# TSAL.net
KiCad netlist of a schematic drawn in Altium Designer
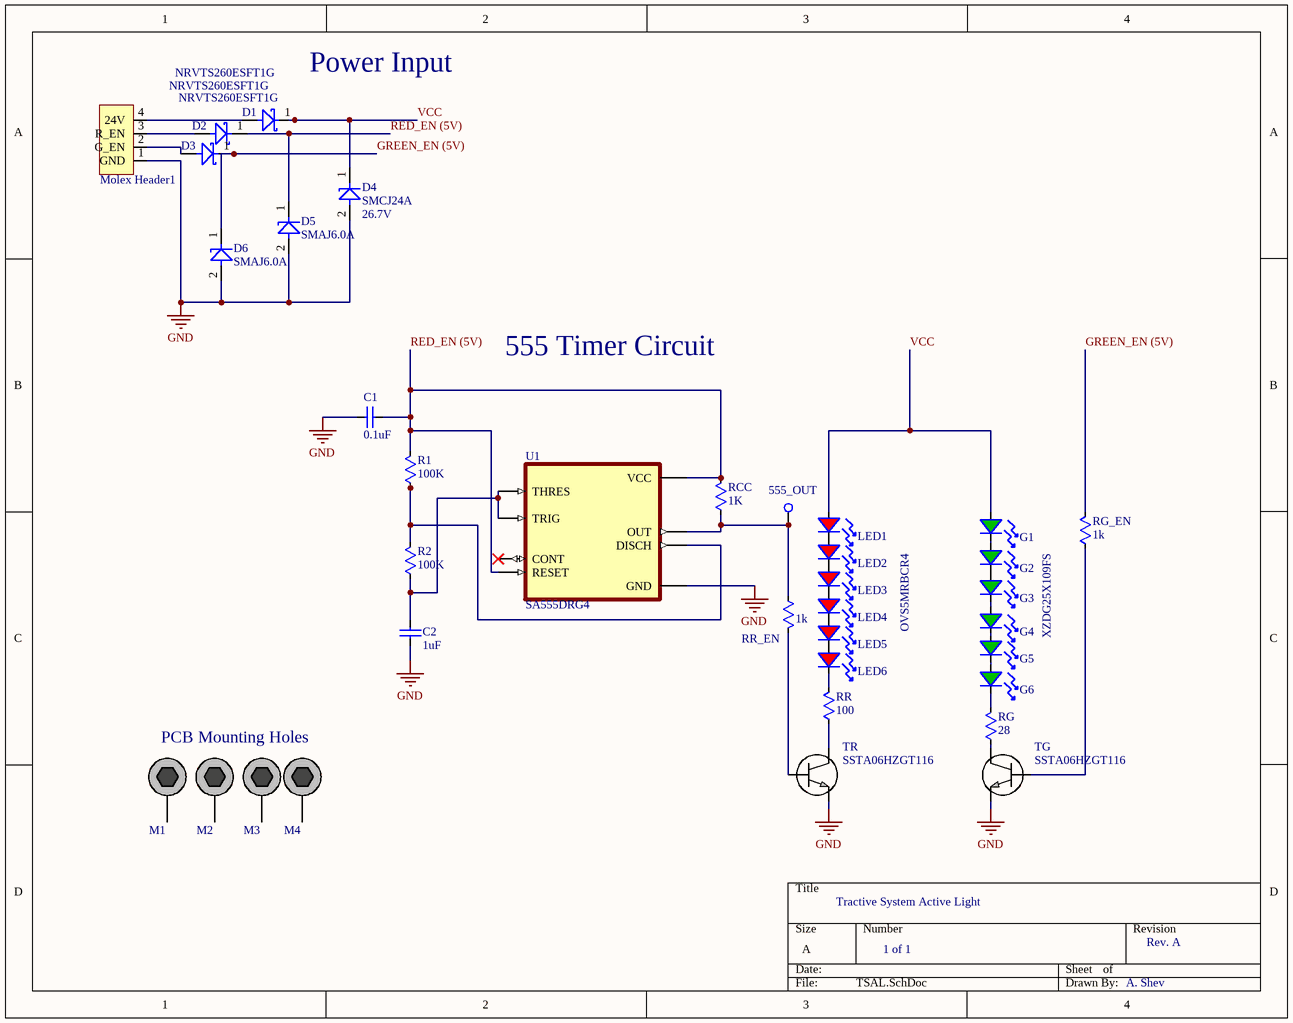
[diagram p0: TSAL.SchDoc]

(export (version "E")
  (design (tool "Eeschema 10.0.6"))
  (components
    (comp (ref "555_OUT")
      (value "Thru-Hole Test Point")
      (footprint "TESTPOINT (THROUGH-HOLE)")
      (libsource (lib "UBC Formula Electric") (part "Thru-Hole Test Point"))
    )
    (comp (ref "C1")
      (value "0.1uF")
      (footprint "0603 CAPACITOR (TDK C-SERIES)")
      (fields (field (name "Comment") "0603"))
      (libsource (lib "UBC Formula Electric") (part "0603 Ceramic Capacitor"))
    )
    (comp (ref "C2")
      (value "1uF")
      (footprint "0603 CAPACITOR (TDK C-SERIES)")
      (description "CAP CER 1UF 25V X5R 0603")
      (fields (field (name "Comment") "0603 CL10A105KA8NNNC"))
      (libsource (lib "UBC Formula Electric") (part "0603 Ceramic Capacitor"))
    )
    (comp (ref "D1")
      (value "NRVTS260ESFT1G")
      (footprint "ON NRVTS260ESFT1G")
      (description "Diode Schottky 60V 2A Surface Mount SOD-123FL")
      (libsource (lib "TSAL_2019_A") (part "ON NRVTS260ESFT1G"))
    )
    (comp (ref "D2")
      (value "NRVTS260ESFT1G")
      (footprint "ON NRVTS260ESFT1G")
      (description "Diode Schottky 60V 2A Surface Mount SOD-123FL")
      (libsource (lib "TSAL_2019_A") (part "ON NRVTS260ESFT1G"))
    )
    (comp (ref "D3")
      (value "NRVTS260ESFT1G")
      (footprint "ON NRVTS260ESFT1G")
      (description "Diode Schottky 60V 2A Surface Mount SOD-123FL")
      (libsource (lib "TSAL_2019_A") (part "ON NRVTS260ESFT1G"))
    )
    (comp (ref "D4")
      (value "SMCJ24A")
      (footprint "LITTELFUSE SMCJ24A")
      (description "38.9V Clamp 38.6A Ipp Tvs Diode Surface Mount DO-214AB (SMCJ)")
      (fields (field (name "ALTIUM_VALUE") "26.7V"))
      (libsource (lib "TSAL_2019_A") (part "Littelfuse SMCJ24A"))
    )
    (comp (ref "D5")
      (value "SMAJ6.0A")
      (footprint "LITTELFUSE SMAJ6.0A")
      (description "10.3V Clamp 38.8A Ipp Tvs Diode Surface Mount DO-214AC (SMA)")
      (libsource (lib "TSAL_2019_A") (part "LF SMAJ6.0A"))
    )
    (comp (ref "D6")
      (value "SMAJ6.0A")
      (footprint "LITTELFUSE SMAJ6.0A")
      (description "10.3V Clamp 38.8A Ipp Tvs Diode Surface Mount DO-214AC (SMA)")
      (libsource (lib "TSAL_2019_A") (part "LF SMAJ6.0A"))
    )
    (comp (ref "G1")
      (value "XZDG25X109FS")
      (footprint "GREEN LED")
      (description "Green 525nm LED Indication - Discrete 3.5V 1411 (3528 Metric)")
      (libsource (lib "Schlib2") (part "GREEN LED"))
    )
    (comp (ref "G2")
      (value "XZDG25X109FS")
      (footprint "GREEN LED")
      (description "Green 525nm LED Indication - Discrete 3.5V 1411 (3528 Metric)")
      (libsource (lib "Schlib2") (part "GREEN LED"))
    )
    (comp (ref "G3")
      (value "XZDG25X109FS")
      (footprint "GREEN LED")
      (description "Green 525nm LED Indication - Discrete 3.5V 1411 (3528 Metric)")
      (libsource (lib "Schlib2") (part "GREEN LED"))
    )
    (comp (ref "G4")
      (value "XZDG25X109FS")
      (footprint "GREEN LED")
      (description "Green 525nm LED Indication - Discrete 3.5V 1411 (3528 Metric)")
      (libsource (lib "Schlib2") (part "GREEN LED"))
    )
    (comp (ref "G5")
      (value "XZDG25X109FS")
      (footprint "GREEN LED")
      (description "Green 525nm LED Indication - Discrete 3.5V 1411 (3528 Metric)")
      (libsource (lib "Schlib2") (part "GREEN LED"))
    )
    (comp (ref "G6")
      (value "XZDG25X109FS")
      (footprint "GREEN LED")
      (description "Green 525nm LED Indication - Discrete 3.5V 1411 (3528 Metric)")
      (libsource (lib "Schlib2") (part "GREEN LED"))
    )
    (comp (ref "LED1")
      (value "OVS5MRBCR4")
      (footprint "RED LED")
      (description "Red 625nm LED Indication - Discrete 2.2V 2-SMD, No Lead")
      (libsource (lib "Schlib2") (part "RED LED"))
    )
    (comp (ref "LED2")
      (value "OVS5MRBCR4")
      (footprint "RED LED")
      (description "Red 625nm LED Indication - Discrete 2.2V 2-SMD, No Lead")
      (libsource (lib "Schlib2") (part "RED LED"))
    )
    (comp (ref "LED3")
      (value "OVS5MRBCR4")
      (footprint "RED LED")
      (description "Red 625nm LED Indication - Discrete 2.2V 2-SMD, No Lead")
      (libsource (lib "Schlib2") (part "RED LED"))
    )
    (comp (ref "LED4")
      (value "OVS5MRBCR4")
      (footprint "RED LED")
      (description "Red 625nm LED Indication - Discrete 2.2V 2-SMD, No Lead")
      (libsource (lib "Schlib2") (part "RED LED"))
    )
    (comp (ref "LED5")
      (value "OVS5MRBCR4")
      (footprint "RED LED")
      (description "Red 625nm LED Indication - Discrete 2.2V 2-SMD, No Lead")
      (libsource (lib "Schlib2") (part "RED LED"))
    )
    (comp (ref "LED6")
      (value "OVS5MRBCR4")
      (footprint "RED LED")
      (description "Red 625nm LED Indication - Discrete 2.2V 2-SMD, No Lead")
      (libsource (lib "Schlib2") (part "RED LED"))
    )
    (comp (ref "M1")
      (value "M1")
      (footprint "M3 SCREW HOLE (Non-Plated)")
      (libsource (lib "UBC Formula Electric") (part "M3 Non-Plated Mounting Holes"))
    )
    (comp (ref "M2")
      (value "M2")
      (footprint "M3 SCREW HOLE (Non-Plated)")
      (libsource (lib "UBC Formula Electric") (part "M3 Non-Plated Mounting Holes"))
    )
    (comp (ref "M3")
      (value "M3")
      (footprint "M3 SCREW HOLE (Non-Plated)")
      (libsource (lib "UBC Formula Electric") (part "M3 Non-Plated Mounting Holes"))
    )
    (comp (ref "M4")
      (value "M4")
      (footprint "M3 SCREW HOLE (Non-Plated)")
      (libsource (lib "UBC Formula Electric") (part "M3 Non-Plated Mounting Holes"))
    )
    (comp (ref "Molex Header1")
      (value "MolexHeader")
      (footprint "4-Pin Bare Wire Pads")
      (libsource (lib "Schlib2") (part "MolexHeader"))
    )
    (comp (ref "R1")
      (value "100K")
      (footprint "0603 RESISTOR (YAGEO)")
      (description "0603 Resistor")
      (fields (field (name "Comment") "0603"))
      (libsource (lib "UBC Formula Electric") (part "0603 Resistor"))
    )
    (comp (ref "R2")
      (value "100K")
      (footprint "0603 RESISTOR (YAGEO)")
      (description "0603 Resistor")
      (fields (field (name "Comment") "0603"))
      (libsource (lib "UBC Formula Electric") (part "0603 Resistor"))
    )
    (comp (ref "RCC")
      (value "1K")
      (footprint "0603 RESISTOR (YAGEO)")
      (description "RES SMD 1 OHM 1% 1/3W 0603")
      (fields (field (name "Comment") "0603"))
      (libsource (lib "UBC Formula Electric") (part "0603 Resistor"))
    )
    (comp (ref "RG")
      (value "28")
      (footprint "0603 RESISTOR (YAGEO)")
      (description "RES SMD 28 OHM 1% 1/3W 0603")
      (fields (field (name "Comment") "0603"))
      (libsource (lib "UBC Formula Electric") (part "0603 Resistor"))
    )
    (comp (ref "RG_EN")
      (value "1k")
      (footprint "0603 RESISTOR (YAGEO)")
      (fields (field (name "Comment") "0603"))
      (libsource (lib "UBC Formula Electric") (part "0603 Resistor"))
    )
    (comp (ref "RR")
      (value "100")
      (footprint "0603 RESISTOR (YAGEO)")
      (description "RES SMD 100 OHM 2% 1.5W 0603")
      (fields (field (name "Comment") "0603"))
      (libsource (lib "UBC Formula Electric") (part "0603 Resistor"))
    )
    (comp (ref "RR_EN")
      (value "1k")
      (footprint "0603 RESISTOR (YAGEO)")
      (fields (field (name "Comment") "0603"))
      (libsource (lib "UBC Formula Electric") (part "0603 Resistor"))
    )
    (comp (ref "TG")
      (value "SSTA06HZGT116")
      (footprint "TRANSISTOR")
      (description "Bipolar (BJT) Transistor NPN 100MHz Surface Mount SST3")
      (fields (field (name "COPYRIGHT") "Copyright (C) 2018 Accelerated Designs. All rights reserved"))
      (libsource (lib "Schlib2") (part "SSTA06HZGT116"))
    )
    (comp (ref "TR")
      (value "SSTA06HZGT116")
      (footprint "TRANSISTOR")
      (description "Bipolar (BJT) Transistor NPN 100MHz Surface Mount SST3")
      (fields (field (name "COPYRIGHT") "Copyright (C) 2018 Accelerated Designs. All rights reserved"))
      (libsource (lib "Schlib2") (part "SSTA06HZGT116"))
    )
    (comp (ref "U1")
      (value "SA555DRG4")
      (footprint "555TIMER")
      (description "Precision timer for -55 to 85C operation 8-SOIC -40 to 85")
      (fields (field (name "MF") "Texas Instruments"))
      (libsource (lib "Schlib2") (part "SA555DRG4"))
    )
  )
  (nets
    (net (code "1") (name "/GREEN_EN (5V)") (class "Default")
      (node (ref "D3") (pin "1") (pinfunction "Cathode_1") (pintype "passive"))
      (node (ref "D6") (pin "1") (pinfunction "1_1") (pintype "passive"))
      (node (ref "RG_EN") (pin "2") (pinfunction "2_2") (pintype "passive"))
    )
    (net (code "2") (name "/RED_EN (5V)") (class "Default")
      (node (ref "C1") (pin "1") (pinfunction "1_1") (pintype "passive"))
      (node (ref "D2") (pin "1") (pinfunction "Cathode_1") (pintype "passive"))
      (node (ref "D5") (pin "1") (pinfunction "1_1") (pintype "passive"))
      (node (ref "R1") (pin "2") (pinfunction "2_2") (pintype "passive"))
      (node (ref "RCC") (pin "2") (pinfunction "2_2") (pintype "passive"))
      (node (ref "U1") (pin "4RESET") (pinfunction "RESET_4RESET") (pintype "input"))
      (node (ref "U1") (pin "8VCC") (pinfunction "VCC_8VCC") (pintype "power_in"))
    )
    (net (code "3") (name "/VCC") (class "Default")
      (node (ref "D1") (pin "1") (pinfunction "Cathode_1") (pintype "passive"))
      (node (ref "D4") (pin "1") (pinfunction "Cathode_1") (pintype "passive"))
      (node (ref "G1") (pin "1") (pinfunction "1_1") (pintype "passive"))
      (node (ref "LED1") (pin "1") (pinfunction "1_1") (pintype "passive"))
    )
    (net (code "4") (name "GND") (class "Default")
      (node (ref "C1") (pin "2") (pinfunction "2_2") (pintype "passive"))
      (node (ref "C2") (pin "2") (pinfunction "2_2") (pintype "passive"))
      (node (ref "D4") (pin "2") (pinfunction "Anode_2") (pintype "passive"))
      (node (ref "D5") (pin "2") (pinfunction "2_2") (pintype "passive"))
      (node (ref "D6") (pin "2") (pinfunction "2_2") (pintype "passive"))
      (node (ref "Molex Header1") (pin "1") (pinfunction "GND_1") (pintype "passive"))
      (node (ref "TG") (pin "1") (pinfunction "Emitter_1") (pintype "passive"))
      (node (ref "TR") (pin "1") (pinfunction "Emitter_1") (pintype "passive"))
      (node (ref "U1") (pin "1GND") (pinfunction "GND_1GND") (pintype "power_in"))
    )
    (net (code "5") (name "Net-(555_OUT-TP)") (class "Default")
      (node (ref "555_OUT") (pin "1") (pinfunction "TP_1") (pintype "passive"))
      (node (ref "RCC") (pin "1") (pinfunction "1_1") (pintype "passive"))
      (node (ref "RR_EN") (pin "1") (pinfunction "1_1") (pintype "passive"))
      (node (ref "U1") (pin "3OUT") (pinfunction "OUT_3OUT") (pintype "output"))
    )
    (net (code "6") (name "Net-(G1-Pad2)") (class "Default")
      (node (ref "G1") (pin "2") (pinfunction "2_2") (pintype "passive"))
      (node (ref "G2") (pin "1") (pinfunction "1_1") (pintype "passive"))
    )
    (net (code "7") (name "Net-(G2-Pad2)") (class "Default")
      (node (ref "G2") (pin "2") (pinfunction "2_2") (pintype "passive"))
      (node (ref "G3") (pin "1") (pinfunction "1_1") (pintype "passive"))
    )
    (net (code "8") (name "Net-(G3-Pad2)") (class "Default")
      (node (ref "G3") (pin "2") (pinfunction "2_2") (pintype "passive"))
      (node (ref "G4") (pin "1") (pinfunction "1_1") (pintype "passive"))
    )
    (net (code "9") (name "Net-(G4-Pad2)") (class "Default")
      (node (ref "G4") (pin "2") (pinfunction "2_2") (pintype "passive"))
      (node (ref "G5") (pin "1") (pinfunction "1_1") (pintype "passive"))
    )
    (net (code "10") (name "Net-(G5-Pad2)") (class "Default")
      (node (ref "G5") (pin "2") (pinfunction "2_2") (pintype "passive"))
      (node (ref "G6") (pin "1") (pinfunction "1_1") (pintype "passive"))
    )
    (net (code "11") (name "Net-(G6-Pad2)") (class "Default")
      (node (ref "G6") (pin "2") (pinfunction "2_2") (pintype "passive"))
      (node (ref "RG") (pin "2") (pinfunction "2_2") (pintype "passive"))
    )
    (net (code "12") (name "Net-(LED1-s)") (class "Default")
      (node (ref "LED1") (pin "2") (pinfunction "s_2") (pintype "passive"))
      (node (ref "LED2") (pin "1") (pinfunction "1_1") (pintype "passive"))
    )
    (net (code "13") (name "Net-(LED2-s)") (class "Default")
      (node (ref "LED2") (pin "2") (pinfunction "s_2") (pintype "passive"))
      (node (ref "LED3") (pin "1") (pinfunction "1_1") (pintype "passive"))
    )
    (net (code "14") (name "Net-(LED3-s)") (class "Default")
      (node (ref "LED3") (pin "2") (pinfunction "s_2") (pintype "passive"))
      (node (ref "LED4") (pin "1") (pinfunction "1_1") (pintype "passive"))
    )
    (net (code "15") (name "Net-(LED4-s)") (class "Default")
      (node (ref "LED4") (pin "2") (pinfunction "s_2") (pintype "passive"))
      (node (ref "LED5") (pin "1") (pinfunction "1_1") (pintype "passive"))
    )
    (net (code "16") (name "Net-(LED5-s)") (class "Default")
      (node (ref "LED5") (pin "2") (pinfunction "s_2") (pintype "passive"))
      (node (ref "LED6") (pin "1") (pinfunction "1_1") (pintype "passive"))
    )
    (net (code "17") (name "Net-(LED6-s)") (class "Default")
      (node (ref "LED6") (pin "2") (pinfunction "s_2") (pintype "passive"))
      (node (ref "RR") (pin "2") (pinfunction "2_2") (pintype "passive"))
    )
    (net (code "18") (name "Net-(Molex Header1-24V)") (class "Default")
      (node (ref "D1") (pin "2") (pinfunction "2_2") (pintype "passive"))
      (node (ref "Molex Header1") (pin "4") (pinfunction "24V_4") (pintype "passive"))
    )
    (net (code "19") (name "Net-(Molex Header1-G_EN)") (class "Default")
      (node (ref "D3") (pin "2") (pinfunction "2_2") (pintype "passive"))
      (node (ref "Molex Header1") (pin "2") (pinfunction "G_EN_2") (pintype "passive"))
    )
    (net (code "20") (name "Net-(Molex Header1-R_EN)") (class "Default")
      (node (ref "D2") (pin "2") (pinfunction "2_2") (pintype "passive"))
      (node (ref "Molex Header1") (pin "3") (pinfunction "R_EN_3") (pintype "passive"))
    )
    (net (code "21") (name "Net-(TG-Base)") (class "Default")
      (node (ref "RG_EN") (pin "1") (pinfunction "1_1") (pintype "passive"))
      (node (ref "TG") (pin "2") (pinfunction "Base_2") (pintype "passive"))
    )
    (net (code "22") (name "Net-(TG-Collector)") (class "Default")
      (node (ref "RG") (pin "1") (pinfunction "1_1") (pintype "passive"))
      (node (ref "TG") (pin "3") (pinfunction "Collector_3") (pintype "passive"))
    )
    (net (code "23") (name "Net-(TR-Base)") (class "Default")
      (node (ref "RR_EN") (pin "2") (pinfunction "2_2") (pintype "passive"))
      (node (ref "TR") (pin "2") (pinfunction "Base_2") (pintype "passive"))
    )
    (net (code "24") (name "Net-(TR-Collector)") (class "Default")
      (node (ref "RR") (pin "1") (pinfunction "1_1") (pintype "passive"))
      (node (ref "TR") (pin "3") (pinfunction "Collector_3") (pintype "passive"))
    )
    (net (code "25") (name "Net-(U1-DISCH)") (class "Default")
      (node (ref "R1") (pin "1") (pinfunction "1_1") (pintype "passive"))
      (node (ref "R2") (pin "2") (pinfunction "2_2") (pintype "passive"))
      (node (ref "U1") (pin "7DISCH") (pinfunction "DISCH_7DISCH") (pintype "output"))
    )
    (net (code "26") (name "Net-(U1-THRES)") (class "Default")
      (node (ref "C2") (pin "1") (pinfunction "1_1") (pintype "passive"))
      (node (ref "R2") (pin "1") (pinfunction "1_1") (pintype "passive"))
      (node (ref "U1") (pin "2TRIG") (pinfunction "TRIG_2TRIG") (pintype "input"))
      (node (ref "U1") (pin "6THRESH") (pinfunction "THRES_6THRESH") (pintype "input"))
    )
    (net (code "27") (name "unconnected-(M1-Pad1)") (class "Default")
      (node (ref "M1") (pin "1") (pinfunction "1_1") (pintype "passive"))
    )
    (net (code "28") (name "unconnected-(M2-Pad1)") (class "Default")
      (node (ref "M2") (pin "1") (pinfunction "1_1") (pintype "passive"))
    )
    (net (code "29") (name "unconnected-(M3-Pad1)") (class "Default")
      (node (ref "M3") (pin "1") (pinfunction "1_1") (pintype "passive"))
    )
    (net (code "30") (name "unconnected-(M4-Pad1)") (class "Default")
      (node (ref "M4") (pin "1") (pinfunction "1_1") (pintype "passive"))
    )
    (net (code "31") (name "unconnected-(U1-CONT-Pad5CONT)") (class "Default")
      (node (ref "U1") (pin "5CONT") (pinfunction "CONT_5CONT") (pintype "bidirectional+no_connect"))
    )
  )
)
